# PCB-Tester-Board.net
KiCad netlist of a schematic drawn in Altium Designer
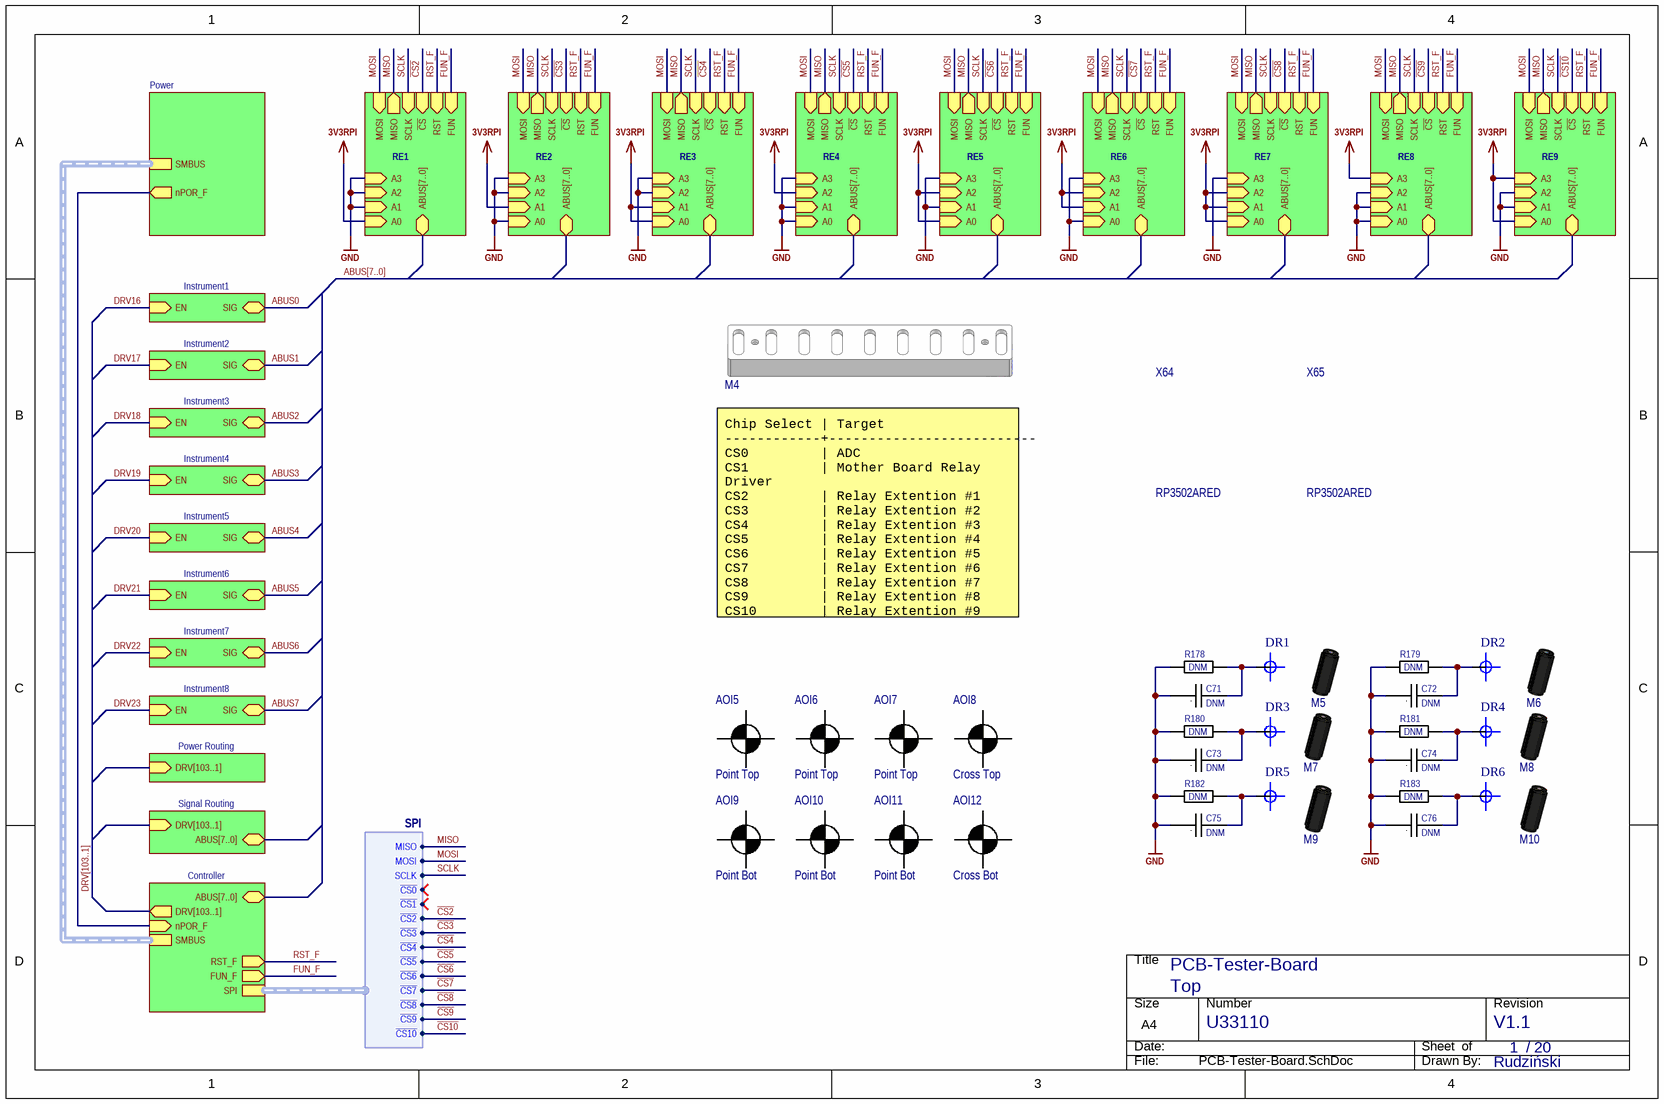
[diagram p0: PCB-Tester-Board.SchDoc]

(export (version "E")
  (design (tool "Eeschema 10.0.6"))
  (components
    (comp (ref "AOI5")
      (value "AOI")
      (footprint "Fiducial Point")
      (description "Assembly AOI")
      (fields (field (name "SHAPE") "Point Top") (field (name "13. CREATED DATE/NAME") "AUG2018/Hören"))
      (libsource (lib "PCB-Tester-Board-V1") (part "Fiducial"))
    )
    (comp (ref "AOI6")
      (value "AOI")
      (footprint "Fiducial Point")
      (description "Assembly AOI")
      (fields (field (name "SHAPE") "Point Top") (field (name "13. CREATED DATE/NAME") "AUG2018/Hören"))
      (libsource (lib "PCB-Tester-Board-V1") (part "Fiducial"))
    )
    (comp (ref "AOI7")
      (value "AOI")
      (footprint "Fiducial Point")
      (description "Assembly AOI")
      (fields (field (name "SHAPE") "Point Top") (field (name "13. CREATED DATE/NAME") "AUG2018/Hören"))
      (libsource (lib "PCB-Tester-Board-V1") (part "Fiducial"))
    )
    (comp (ref "AOI8")
      (value "AOI")
      (footprint "Fiducial Cross")
      (description "Assembly AOI")
      (fields (field (name "SHAPE") "Cross Top") (field (name "13. CREATED DATE/NAME") "AUG2018/Hören"))
      (libsource (lib "PCB-Tester-Board-V1") (part "Fiducial"))
    )
    (comp (ref "AOI9")
      (value "AOI")
      (footprint "Fiducial Point")
      (description "Assembly AOI")
      (fields (field (name "SHAPE") "Point Bot") (field (name "13. CREATED DATE/NAME") "AUG2018/Hören"))
      (libsource (lib "PCB-Tester-Board-V1") (part "Fiducial"))
    )
    (comp (ref "AOI10")
      (value "AOI")
      (footprint "Fiducial Point")
      (description "Assembly AOI")
      (fields (field (name "SHAPE") "Point Bot") (field (name "13. CREATED DATE/NAME") "AUG2018/Hören"))
      (libsource (lib "PCB-Tester-Board-V1") (part "Fiducial"))
    )
    (comp (ref "AOI11")
      (value "AOI")
      (footprint "Fiducial Point")
      (description "Assembly AOI")
      (fields (field (name "SHAPE") "Point Bot") (field (name "13. CREATED DATE/NAME") "AUG2018/Hören"))
      (libsource (lib "PCB-Tester-Board-V1") (part "Fiducial"))
    )
    (comp (ref "AOI12")
      (value "AOI")
      (footprint "Fiducial Cross")
      (description "Assembly AOI")
      (fields (field (name "SHAPE") "Cross Bot") (field (name "13. CREATED DATE/NAME") "AUG2018/Hören"))
      (libsource (lib "PCB-Tester-Board-V1") (part "Fiducial"))
    )
    (comp (ref "C71")
      (value "DNM")
      (footprint "C1206 Reflow")
      (description "Capacitor Unpolarized")
      (fields
        (field (name "TOLERANCE") "±20%")
        (field (name "Comment") "C")
        (field (name "13. CREATED DATE/NAME") "AUG2018/Hören")
      )
      (libsource (lib "chickenfood") (part "C"))
    )
    (comp (ref "C72")
      (value "DNM")
      (footprint "C1206 Reflow")
      (description "Capacitor Unpolarized")
      (fields
        (field (name "TOLERANCE") "±20%")
        (field (name "Comment") "C")
        (field (name "13. CREATED DATE/NAME") "AUG2018/Hören")
      )
      (libsource (lib "chickenfood") (part "C"))
    )
    (comp (ref "C73")
      (value "DNM")
      (footprint "C1206 Reflow")
      (description "Capacitor Unpolarized")
      (fields
        (field (name "TOLERANCE") "±20%")
        (field (name "Comment") "C")
        (field (name "13. CREATED DATE/NAME") "AUG2018/Hören")
      )
      (libsource (lib "chickenfood") (part "C"))
    )
    (comp (ref "C74")
      (value "DNM")
      (footprint "C1206 Reflow")
      (description "Capacitor Unpolarized")
      (fields
        (field (name "TOLERANCE") "±20%")
        (field (name "Comment") "C")
        (field (name "13. CREATED DATE/NAME") "AUG2018/Hören")
      )
      (libsource (lib "chickenfood") (part "C"))
    )
    (comp (ref "C75")
      (value "DNM")
      (footprint "C1206 Reflow")
      (description "Capacitor Unpolarized")
      (fields
        (field (name "TOLERANCE") "±20%")
        (field (name "Comment") "C")
        (field (name "13. CREATED DATE/NAME") "AUG2018/Hören")
      )
      (libsource (lib "chickenfood") (part "C"))
    )
    (comp (ref "C76")
      (value "DNM")
      (footprint "C1206 Reflow")
      (description "Capacitor Unpolarized")
      (fields
        (field (name "TOLERANCE") "±20%")
        (field (name "Comment") "C")
        (field (name "13. CREATED DATE/NAME") "AUG2018/Hören")
      )
      (libsource (lib "chickenfood") (part "C"))
    )
    (comp (ref "DR1")
      (value "X")
      (footprint "HOLE_3.4mm")
      (description "Fiducal 90 mil")
      (libsource (lib "SchLib1") (part "Drill-3.2mm-M3-C"))
    )
    (comp (ref "DR2")
      (value "X")
      (footprint "HOLE_3.4mm")
      (description "Fiducal 90 mil")
      (libsource (lib "SchLib1") (part "Drill-3.2mm-M3-C"))
    )
    (comp (ref "DR3")
      (value "X")
      (footprint "HOLE_3.4mm")
      (description "Fiducal 90 mil")
      (libsource (lib "SchLib1") (part "Drill-3.2mm-M3-C"))
    )
    (comp (ref "DR4")
      (value "X")
      (footprint "HOLE_3.4mm")
      (description "Fiducal 90 mil")
      (libsource (lib "SchLib1") (part "Drill-3.2mm-M3-C"))
    )
    (comp (ref "DR5")
      (value "X")
      (footprint "HOLE_3.4mm")
      (description "Fiducal 90 mil")
      (libsource (lib "SchLib1") (part "Drill-3.2mm-M3-C"))
    )
    (comp (ref "DR6")
      (value "X")
      (footprint "HOLE_3.4mm")
      (description "Fiducal 90 mil")
      (libsource (lib "SchLib1") (part "Drill-3.2mm-M3-C"))
    )
    (comp (ref "M4")
      (value "M")
      (description "Support Block")
      (fields (field (name "13. CREATED DATE/NAME") "??? / Hören"))
      (libsource (lib "PCB-Tester-Board") (part "Support Block"))
    )
    (comp (ref "M5")
      (value "M")
      (footprint "970180155")
      (description "PLASTIC SPACER STUD METRIC THREA")
      (fields
        (field (name "02. DISTRIBUTOR PART NUMBER") "732-13017-ND")
        (field (name "07. MANUFACTURER  PART NUMBER") "970180155")
        (field (name "13. CREATED DATE/NAME") "??? / Hören")
      )
      (libsource (lib "PCB-Tester-Board") (part "Spacer 18mm Plastic"))
    )
    (comp (ref "M6")
      (value "M")
      (footprint "970180155")
      (description "PLASTIC SPACER STUD METRIC THREA")
      (fields
        (field (name "02. DISTRIBUTOR PART NUMBER") "732-13017-ND")
        (field (name "07. MANUFACTURER  PART NUMBER") "970180155")
        (field (name "13. CREATED DATE/NAME") "??? / Hören")
      )
      (libsource (lib "PCB-Tester-Board") (part "Spacer 18mm Plastic"))
    )
    (comp (ref "M7")
      (value "M")
      (footprint "970180155")
      (description "PLASTIC SPACER STUD METRIC THREA")
      (fields
        (field (name "02. DISTRIBUTOR PART NUMBER") "732-13017-ND")
        (field (name "07. MANUFACTURER  PART NUMBER") "970180155")
        (field (name "13. CREATED DATE/NAME") "??? / Hören")
      )
      (libsource (lib "PCB-Tester-Board") (part "Spacer 18mm Plastic"))
    )
    (comp (ref "M8")
      (value "M")
      (footprint "970180155")
      (description "PLASTIC SPACER STUD METRIC THREA")
      (fields
        (field (name "02. DISTRIBUTOR PART NUMBER") "732-13017-ND")
        (field (name "07. MANUFACTURER  PART NUMBER") "970180155")
        (field (name "13. CREATED DATE/NAME") "??? / Hören")
      )
      (libsource (lib "PCB-Tester-Board") (part "Spacer 18mm Plastic"))
    )
    (comp (ref "M9")
      (value "M")
      (footprint "970180155")
      (description "PLASTIC SPACER STUD METRIC THREA")
      (fields
        (field (name "02. DISTRIBUTOR PART NUMBER") "732-13017-ND")
        (field (name "07. MANUFACTURER  PART NUMBER") "970180155")
        (field (name "13. CREATED DATE/NAME") "??? / Hören")
      )
      (libsource (lib "PCB-Tester-Board") (part "Spacer 18mm Plastic"))
    )
    (comp (ref "M10")
      (value "M")
      (footprint "970180155")
      (description "PLASTIC SPACER STUD METRIC THREA")
      (fields
        (field (name "02. DISTRIBUTOR PART NUMBER") "732-13017-ND")
        (field (name "07. MANUFACTURER  PART NUMBER") "970180155")
        (field (name "13. CREATED DATE/NAME") "??? / Hören")
      )
      (libsource (lib "PCB-Tester-Board") (part "Spacer 18mm Plastic"))
    )
    (comp (ref "R178")
      (value "DNM")
      (footprint "R1206 Reflow")
      (description "Resistor")
      (fields
        (field (name "TOLERANCE") "±1%")
        (field (name "Comment") "R")
        (field (name "13. CREATED DATE/NAME") "AUG2018/Hören")
      )
      (libsource (lib "chickenfood") (part "R"))
    )
    (comp (ref "R179")
      (value "DNM")
      (footprint "R1206 Reflow")
      (description "Resistor")
      (fields
        (field (name "TOLERANCE") "±1%")
        (field (name "Comment") "R")
        (field (name "13. CREATED DATE/NAME") "AUG2018/Hören")
      )
      (libsource (lib "chickenfood") (part "R"))
    )
    (comp (ref "R180")
      (value "DNM")
      (footprint "R1206 Reflow")
      (description "Resistor")
      (fields
        (field (name "TOLERANCE") "±1%")
        (field (name "Comment") "R")
        (field (name "13. CREATED DATE/NAME") "AUG2018/Hören")
      )
      (libsource (lib "chickenfood") (part "R"))
    )
    (comp (ref "R181")
      (value "DNM")
      (footprint "R1206 Reflow")
      (description "Resistor")
      (fields
        (field (name "TOLERANCE") "±1%")
        (field (name "Comment") "R")
        (field (name "13. CREATED DATE/NAME") "AUG2018/Hören")
      )
      (libsource (lib "chickenfood") (part "R"))
    )
    (comp (ref "R182")
      (value "DNM")
      (footprint "R1206 Reflow")
      (description "Resistor")
      (fields
        (field (name "TOLERANCE") "±1%")
        (field (name "Comment") "R")
        (field (name "13. CREATED DATE/NAME") "AUG2018/Hören")
      )
      (libsource (lib "chickenfood") (part "R"))
    )
    (comp (ref "R183")
      (value "DNM")
      (footprint "R1206 Reflow")
      (description "Resistor")
      (fields
        (field (name "TOLERANCE") "±1%")
        (field (name "Comment") "R")
        (field (name "13. CREATED DATE/NAME") "AUG2018/Hören")
      )
      (libsource (lib "chickenfood") (part "R"))
    )
    (comp (ref "X64")
      (value "X")
      (description "SWITCH PUSH SPST-NO 3A 120V")
      (fields
        (field (name "02. DISTRIBUTOR PART NUMBER") "EG1930-ND")
        (field (name "07. MANUFACTURER  PART NUMBER") "RP3502ARED")
        (field (name "13. CREATED DATE/NAME") "AUG 2018 / Hören")
      )
      (libsource (lib "PCB-Tester-Board") (part "RP3502ARED"))
    )
    (comp (ref "X65")
      (value "X")
      (description "SWITCH PUSH SPST-NO 3A 120V")
      (fields
        (field (name "02. DISTRIBUTOR PART NUMBER") "EG1930-ND")
        (field (name "07. MANUFACTURER  PART NUMBER") "RP3502ARED")
        (field (name "13. CREATED DATE/NAME") "AUG 2018 / Hören")
      )
      (libsource (lib "PCB-Tester-Board") (part "RP3502ARED"))
    )
  )
  (nets
    (net (code "143") (name "GND") (class "Default")
      (node (ref "C71") (pin "1") (pinfunction "1_1") (pintype "passive"))
      (node (ref "C72") (pin "1") (pinfunction "1_1") (pintype "passive"))
      (node (ref "C73") (pin "1") (pinfunction "1_1") (pintype "passive"))
      (node (ref "C74") (pin "1") (pinfunction "1_1") (pintype "passive"))
      (node (ref "C75") (pin "1") (pinfunction "1_1") (pintype "passive"))
      (node (ref "C76") (pin "1") (pinfunction "1_1") (pintype "passive"))
      (node (ref "R178") (pin "2") (pinfunction "2_2") (pintype "passive"))
      (node (ref "R179") (pin "2") (pinfunction "2_2") (pintype "passive"))
      (node (ref "R180") (pin "2") (pinfunction "2_2") (pintype "passive"))
      (node (ref "R181") (pin "2") (pinfunction "2_2") (pintype "passive"))
      (node (ref "R182") (pin "2") (pinfunction "2_2") (pintype "passive"))
      (node (ref "R183") (pin "2") (pinfunction "2_2") (pintype "passive"))
    )
    (net (code "144") (name "Net-(DR1-OUT3)") (class "Default")
      (node (ref "C71") (pin "2") (pinfunction "2_2") (pintype "passive"))
      (node (ref "DR1") (pin "1") (pinfunction "OUT3_1") (pintype "passive"))
      (node (ref "R178") (pin "1") (pinfunction "1_1") (pintype "passive"))
    )
    (net (code "145") (name "Net-(DR2-OUT3)") (class "Default")
      (node (ref "C72") (pin "2") (pinfunction "2_2") (pintype "passive"))
      (node (ref "DR2") (pin "1") (pinfunction "OUT3_1") (pintype "passive"))
      (node (ref "R179") (pin "1") (pinfunction "1_1") (pintype "passive"))
    )
    (net (code "146") (name "Net-(DR3-OUT3)") (class "Default")
      (node (ref "C73") (pin "2") (pinfunction "2_2") (pintype "passive"))
      (node (ref "DR3") (pin "1") (pinfunction "OUT3_1") (pintype "passive"))
      (node (ref "R180") (pin "1") (pinfunction "1_1") (pintype "passive"))
    )
    (net (code "147") (name "Net-(DR4-OUT3)") (class "Default")
      (node (ref "C74") (pin "2") (pinfunction "2_2") (pintype "passive"))
      (node (ref "DR4") (pin "1") (pinfunction "OUT3_1") (pintype "passive"))
      (node (ref "R181") (pin "1") (pinfunction "1_1") (pintype "passive"))
    )
    (net (code "148") (name "Net-(DR5-OUT3)") (class "Default")
      (node (ref "C75") (pin "2") (pinfunction "2_2") (pintype "passive"))
      (node (ref "DR5") (pin "1") (pinfunction "OUT3_1") (pintype "passive"))
      (node (ref "R182") (pin "1") (pinfunction "1_1") (pintype "passive"))
    )
    (net (code "149") (name "Net-(DR6-OUT3)") (class "Default")
      (node (ref "C76") (pin "2") (pinfunction "2_2") (pintype "passive"))
      (node (ref "DR6") (pin "1") (pinfunction "OUT3_1") (pintype "passive"))
      (node (ref "R183") (pin "1") (pinfunction "1_1") (pintype "passive"))
    )
  )
)
